# v1.net
KiCad netlist of a schematic drawn in EAGLE
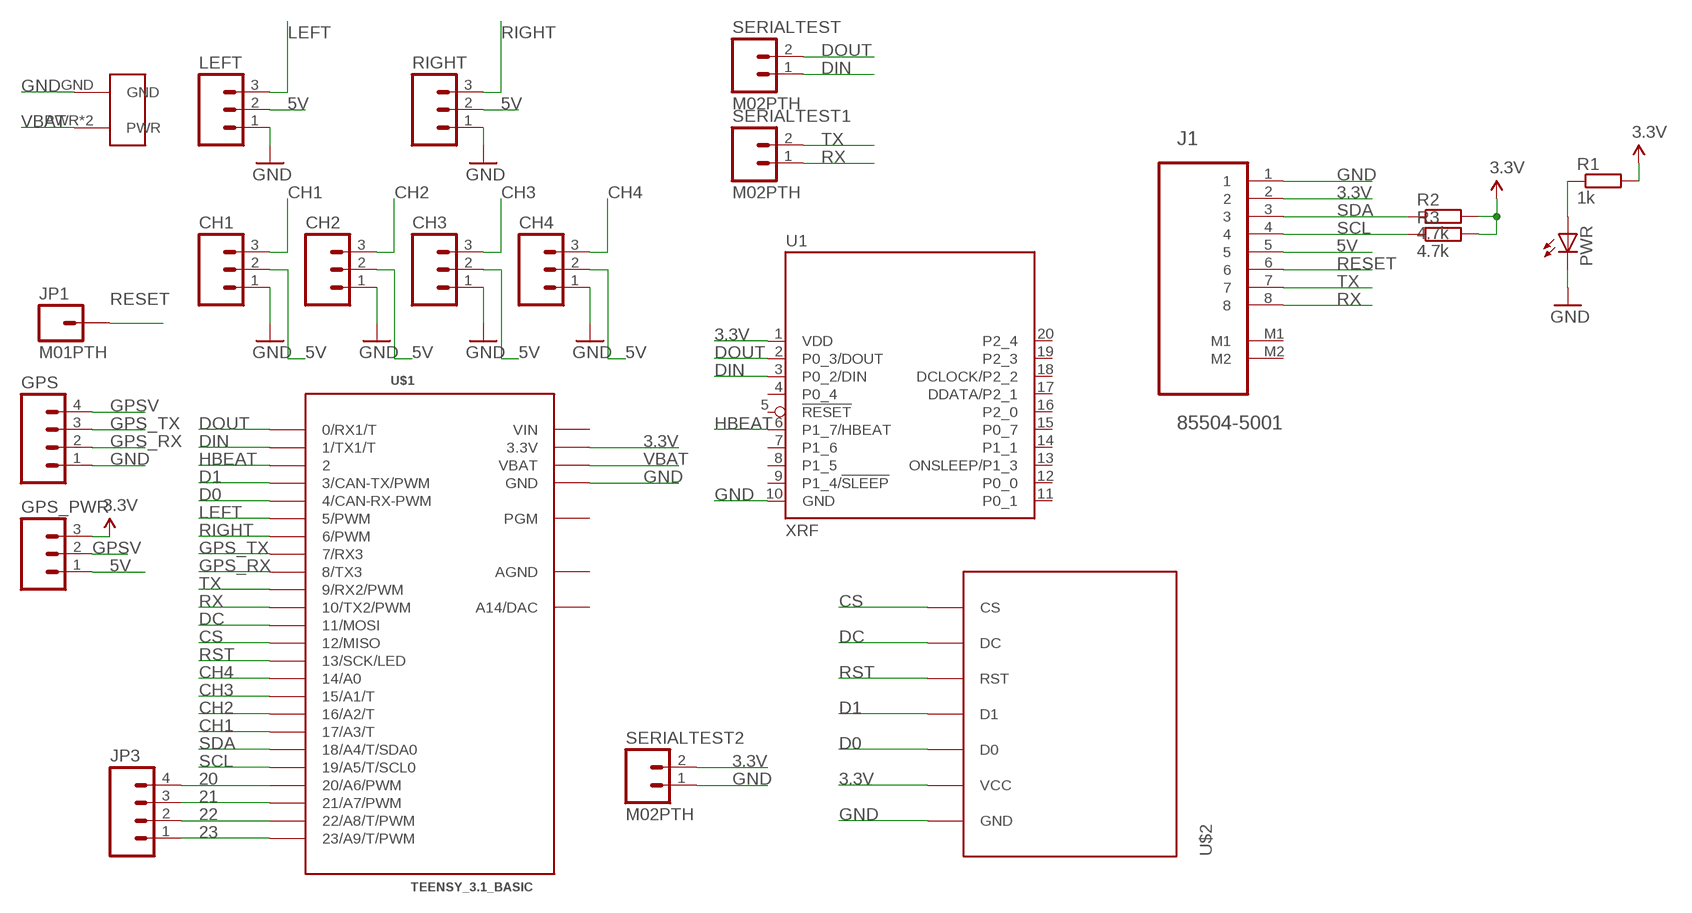
[diagram p0: schematic, sheet 1]

(export (version "E")
  (design (tool "Eeschema 10.0.6"))
  (components
    (comp (ref "CH1")
      (value "M03PTH")
      (footprint "eagle-import:1X03")
      (libsource (lib "eagle-import") (part "M03PTH"))
    )
    (comp (ref "CH2")
      (value "M03PTH")
      (footprint "eagle-import:1X03")
      (libsource (lib "eagle-import") (part "M03PTH"))
    )
    (comp (ref "CH3")
      (value "M03PTH")
      (footprint "eagle-import:1X03")
      (libsource (lib "eagle-import") (part "M03PTH"))
    )
    (comp (ref "CH4")
      (value "M03PTH")
      (footprint "eagle-import:1X03")
      (libsource (lib "eagle-import") (part "M03PTH"))
    )
    (comp (ref "GPS")
      (value "M04PTH")
      (footprint "eagle-import:1X04")
      (libsource (lib "eagle-import") (part "M04PTH"))
    )
    (comp (ref "GPS_PWR")
      (value "M03PTH")
      (footprint "eagle-import:1X03")
      (libsource (lib "eagle-import") (part "M03PTH"))
    )
    (comp (ref "J1")
      (value "85504-5001")
      (footprint "eagle-import:MOLEX_85504-5001")
      (libsource (lib "eagle-import") (part "85504-5001"))
    )
    (comp (ref "JP1")
      (value "M01PTH")
      (footprint "eagle-import:1X01")
      (libsource (lib "eagle-import") (part "M01PTH"))
    )
    (comp (ref "JP3")
      (value "M04PTH")
      (footprint "eagle-import:1X04")
      (libsource (lib "eagle-import") (part "M04PTH"))
    )
    (comp (ref "LEFT")
      (value "M03PTH")
      (footprint "eagle-import:1X03")
      (libsource (lib "eagle-import") (part "M03PTH"))
    )
    (comp (ref "PWR")
      (value "LEDCHIPLED_0805")
      (footprint "eagle-import:CHIPLED_0805")
      (libsource (lib "eagle-import") (part "LEDCHIPLED_0805"))
    )
    (comp (ref "R1")
      (value "1k")
      (footprint "eagle-import:R0805")
      (libsource (lib "eagle-import") (part "R-EU_R0805"))
    )
    (comp (ref "R2")
      (value "4.7k")
      (footprint "eagle-import:R0805")
      (libsource (lib "eagle-import") (part "R-EU_R0805"))
    )
    (comp (ref "R3")
      (value "4.7k")
      (footprint "eagle-import:R0805")
      (libsource (lib "eagle-import") (part "R-EU_R0805"))
    )
    (comp (ref "RIGHT")
      (value "M03PTH")
      (footprint "eagle-import:1X03")
      (libsource (lib "eagle-import") (part "M03PTH"))
    )
    (comp (ref "SERIALTEST")
      (value "M02PTH")
      (footprint "eagle-import:1X02")
      (libsource (lib "eagle-import") (part "M02PTH"))
    )
    (comp (ref "SERIALTEST1")
      (value "M02PTH")
      (footprint "eagle-import:1X02")
      (libsource (lib "eagle-import") (part "M02PTH"))
    )
    (comp (ref "SERIALTEST2")
      (value "M02PTH")
      (footprint "eagle-import:1X02")
      (libsource (lib "eagle-import") (part "M02PTH"))
    )
    (comp (ref "U$1")
      (value "TEENSY_3.1_BASIC")
      (footprint "eagle-import:TEENSY_3.1_BASIC")
      (libsource (lib "eagle-import") (part "TEENSY_3.1_BASIC"))
    )
    (comp (ref "U$2")
      (value "OLED_SSD1306_SPI")
      (footprint "eagle-import:OLED_SSD1306_SPI")
      (libsource (lib "eagle-import") (part "OLED_SSD1306_SPI"))
    )
    (comp (ref "U$3")
      (value "COINCELL")
      (footprint "eagle-import:COINCELL")
      (libsource (lib "eagle-import") (part "COINCELL"))
    )
    (comp (ref "U1")
      (value "XRF")
      (footprint "eagle-import:XRF")
      (libsource (lib "eagle-import") (part "XRF"))
    )
  )
  (nets
    (net (code "1") (name "/5V") (class "Default")
      (node (ref "CH1") (pin "2") (pinfunction "2_2") (pintype "passive"))
      (node (ref "CH2") (pin "2") (pinfunction "2_2") (pintype "passive"))
      (node (ref "CH3") (pin "2") (pinfunction "2_2") (pintype "passive"))
      (node (ref "CH4") (pin "2") (pinfunction "2_2") (pintype "passive"))
      (node (ref "GPS_PWR") (pin "1") (pinfunction "1_1") (pintype "passive"))
      (node (ref "J1") (pin "5") (pinfunction "5_5") (pintype "bidirectional"))
      (node (ref "LEFT") (pin "2") (pinfunction "2_2") (pintype "passive"))
      (node (ref "RIGHT") (pin "2") (pinfunction "2_2") (pintype "passive"))
    )
    (net (code "2") (name "/20") (class "Default")
      (node (ref "JP3") (pin "4") (pinfunction "4_4") (pintype "passive"))
      (node (ref "U$1") (pin "20/A6") (pinfunction "20/A6/PWM_20/A6") (pintype "bidirectional"))
    )
    (net (code "3") (name "/21") (class "Default")
      (node (ref "JP3") (pin "3") (pinfunction "3_3") (pintype "passive"))
      (node (ref "U$1") (pin "21/A7") (pinfunction "21/A7/PWM_21/A7") (pintype "bidirectional"))
    )
    (net (code "4") (name "/22") (class "Default")
      (node (ref "JP3") (pin "2") (pinfunction "2_2") (pintype "passive"))
      (node (ref "U$1") (pin "22/A8") (pinfunction "22/A8/T/PWM_22/A8") (pintype "bidirectional"))
    )
    (net (code "5") (name "/23") (class "Default")
      (node (ref "JP3") (pin "1") (pinfunction "1_1") (pintype "passive"))
      (node (ref "U$1") (pin "23/A9") (pinfunction "23/A9/T/PWM_23/A9") (pintype "bidirectional"))
    )
    (net (code "6") (name "/AGND") (class "Default")
      (node (ref "U$1") (pin "AGND") (pinfunction "AGND_AGND") (pintype "power_in"))
    )
    (net (code "7") (name "/CH1") (class "Default")
      (node (ref "CH1") (pin "3") (pinfunction "3_3") (pintype "passive"))
      (node (ref "U$1") (pin "17/A3") (pinfunction "17/A3/T_17/A3") (pintype "bidirectional"))
    )
    (net (code "8") (name "/CH2") (class "Default")
      (node (ref "CH2") (pin "3") (pinfunction "3_3") (pintype "passive"))
      (node (ref "U$1") (pin "16/A2") (pinfunction "16/A2/T_16/A2") (pintype "bidirectional"))
    )
    (net (code "9") (name "/CH3") (class "Default")
      (node (ref "CH3") (pin "3") (pinfunction "3_3") (pintype "passive"))
      (node (ref "U$1") (pin "15/A1") (pinfunction "15/A1/T_15/A1") (pintype "bidirectional"))
    )
    (net (code "10") (name "/CH4") (class "Default")
      (node (ref "CH4") (pin "3") (pinfunction "3_3") (pintype "passive"))
      (node (ref "U$1") (pin "14/A0") (pinfunction "14/A0_14/A0") (pintype "bidirectional"))
    )
    (net (code "11") (name "/CS") (class "Default")
      (node (ref "U$1") (pin "12") (pinfunction "12/MISO_12") (pintype "bidirectional"))
      (node (ref "U$2") (pin "CS") (pinfunction "CS_CS") (pintype "bidirectional"))
    )
    (net (code "12") (name "/D0") (class "Default")
      (node (ref "U$1") (pin "4") (pinfunction "4/CAN-RX-PWM_4") (pintype "bidirectional"))
      (node (ref "U$2") (pin "D0") (pinfunction "D0_D0") (pintype "bidirectional"))
    )
    (net (code "13") (name "/D1") (class "Default")
      (node (ref "U$1") (pin "3") (pinfunction "3/CAN-TX/PWM_3") (pintype "bidirectional"))
      (node (ref "U$2") (pin "D1") (pinfunction "D1_D1") (pintype "bidirectional"))
    )
    (net (code "14") (name "/DC") (class "Default")
      (node (ref "U$1") (pin "11") (pinfunction "11/MOSI_11") (pintype "bidirectional"))
      (node (ref "U$2") (pin "DC") (pinfunction "DC_DC") (pintype "bidirectional"))
    )
    (net (code "15") (name "/DIN") (class "Default")
      (node (ref "SERIALTEST") (pin "1") (pinfunction "1_1") (pintype "passive"))
      (node (ref "U$1") (pin "1") (pinfunction "1/TX1/T_1") (pintype "bidirectional"))
      (node (ref "U1") (pin "3") (pinfunction "P0_2/DIN_3") (pintype "input"))
    )
    (net (code "16") (name "/DOUT") (class "Default")
      (node (ref "SERIALTEST") (pin "2") (pinfunction "2_2") (pintype "passive"))
      (node (ref "U$1") (pin "0") (pinfunction "0/RX1/T_0") (pintype "bidirectional"))
      (node (ref "U1") (pin "2") (pinfunction "P0_3/DOUT_2") (pintype "output"))
    )
    (net (code "17") (name "/GPSV") (class "Default")
      (node (ref "GPS") (pin "4") (pinfunction "4_4") (pintype "passive"))
      (node (ref "GPS_PWR") (pin "2") (pinfunction "2_2") (pintype "passive"))
    )
    (net (code "18") (name "/GPS_RX") (class "Default")
      (node (ref "GPS") (pin "2") (pinfunction "2_2") (pintype "passive"))
      (node (ref "U$1") (pin "8") (pinfunction "8/TX3_8") (pintype "bidirectional"))
    )
    (net (code "19") (name "/GPS_TX") (class "Default")
      (node (ref "GPS") (pin "3") (pinfunction "3_3") (pintype "passive"))
      (node (ref "U$1") (pin "7") (pinfunction "7/RX3_7") (pintype "bidirectional"))
    )
    (net (code "20") (name "/HBEAT") (class "Default")
      (node (ref "U$1") (pin "2") (pinfunction "2_2") (pintype "bidirectional"))
      (node (ref "U1") (pin "6") (pinfunction "P1_7/HBEAT_6") (pintype "bidirectional"))
    )
    (net (code "21") (name "/LEFT") (class "Default")
      (node (ref "LEFT") (pin "3") (pinfunction "3_3") (pintype "passive"))
      (node (ref "U$1") (pin "5") (pinfunction "5/PWM_5") (pintype "bidirectional"))
    )
    (net (code "22") (name "/RESET") (class "Default")
      (node (ref "J1") (pin "6") (pinfunction "6_6") (pintype "bidirectional"))
      (node (ref "JP1") (pin "1") (pinfunction "1_1") (pintype "passive"))
    )
    (net (code "23") (name "/RIGHT") (class "Default")
      (node (ref "RIGHT") (pin "3") (pinfunction "3_3") (pintype "passive"))
      (node (ref "U$1") (pin "6") (pinfunction "6/PWM_6") (pintype "bidirectional"))
    )
    (net (code "24") (name "/RST") (class "Default")
      (node (ref "U$1") (pin "13") (pinfunction "13/SCK/LED_13") (pintype "bidirectional"))
      (node (ref "U$2") (pin "RST") (pinfunction "RST_RST") (pintype "bidirectional"))
    )
    (net (code "25") (name "/RX") (class "Default")
      (node (ref "J1") (pin "8") (pinfunction "8_8") (pintype "bidirectional"))
      (node (ref "SERIALTEST1") (pin "1") (pinfunction "1_1") (pintype "passive"))
      (node (ref "U$1") (pin "10") (pinfunction "10/TX2/PWM_10") (pintype "bidirectional"))
    )
    (net (code "26") (name "/SCL") (class "Default")
      (node (ref "J1") (pin "4") (pinfunction "4_4") (pintype "bidirectional"))
      (node (ref "R3") (pin "1") (pinfunction "1_1") (pintype "passive"))
      (node (ref "U$1") (pin "19/A5") (pinfunction "19/A5/T/SCL0_19/A5") (pintype "bidirectional"))
    )
    (net (code "27") (name "/SDA") (class "Default")
      (node (ref "J1") (pin "3") (pinfunction "3_3") (pintype "bidirectional"))
      (node (ref "R2") (pin "1") (pinfunction "1_1") (pintype "passive"))
      (node (ref "U$1") (pin "18/A4") (pinfunction "18/A4/T/SDA0_18/A4") (pintype "bidirectional"))
    )
    (net (code "28") (name "/TX") (class "Default")
      (node (ref "J1") (pin "7") (pinfunction "7_7") (pintype "bidirectional"))
      (node (ref "SERIALTEST1") (pin "2") (pinfunction "2_2") (pintype "passive"))
      (node (ref "U$1") (pin "9") (pinfunction "9/RX2/PWM_9") (pintype "bidirectional"))
    )
    (net (code "29") (name "/VBAT") (class "Default")
      (node (ref "U$1") (pin "VBAT") (pinfunction "VBAT_VBAT") (pintype "power_in"))
      (node (ref "U$3") (pin "PWR") (pinfunction "PWR_PWR") (pintype "bidirectional"))
      (node (ref "U$3") (pin "PWR2") (pinfunction "PWR_PWR2") (pintype "bidirectional"))
    )
    (net (code "30") (name "/VIN") (class "Default")
      (node (ref "U$1") (pin "VIN") (pinfunction "VIN_VIN") (pintype "power_in"))
    )
    (net (code "31") (name "3.3V") (class "Default")
      (node (ref "GPS_PWR") (pin "3") (pinfunction "3_3") (pintype "passive"))
      (node (ref "J1") (pin "2") (pinfunction "2_2") (pintype "bidirectional"))
      (node (ref "R1") (pin "2") (pinfunction "2_2") (pintype "passive"))
      (node (ref "R2") (pin "2") (pinfunction "2_2") (pintype "passive"))
      (node (ref "R3") (pin "2") (pinfunction "2_2") (pintype "passive"))
      (node (ref "SERIALTEST2") (pin "2") (pinfunction "2_2") (pintype "passive"))
      (node (ref "U$1") (pin "3.3V") (pinfunction "3.3V_3.3V") (pintype "power_in"))
      (node (ref "U$1") (pin "3.3V1") (pinfunction "3.3V_3.3V1") (pintype "power_in"))
      (node (ref "U$2") (pin "VCC") (pinfunction "VCC_VCC") (pintype "bidirectional"))
      (node (ref "U1") (pin "1") (pinfunction "VDD_1") (pintype "power_in"))
    )
    (net (code "32") (name "GND") (class "Default")
      (node (ref "CH1") (pin "1") (pinfunction "1_1") (pintype "passive"))
      (node (ref "CH2") (pin "1") (pinfunction "1_1") (pintype "passive"))
      (node (ref "CH3") (pin "1") (pinfunction "1_1") (pintype "passive"))
      (node (ref "CH4") (pin "1") (pinfunction "1_1") (pintype "passive"))
      (node (ref "GPS") (pin "1") (pinfunction "1_1") (pintype "passive"))
      (node (ref "J1") (pin "1") (pinfunction "1_1") (pintype "bidirectional"))
      (node (ref "LEFT") (pin "1") (pinfunction "1_1") (pintype "passive"))
      (node (ref "PWR") (pin "C") (pinfunction "C_C") (pintype "passive"))
      (node (ref "RIGHT") (pin "1") (pinfunction "1_1") (pintype "passive"))
      (node (ref "SERIALTEST2") (pin "1") (pinfunction "1_1") (pintype "passive"))
      (node (ref "U$1") (pin "GND") (pinfunction "GND_GND") (pintype "power_in"))
      (node (ref "U$1") (pin "GND1") (pinfunction "GND_GND1") (pintype "power_in"))
      (node (ref "U$2") (pin "GND") (pinfunction "GND_GND") (pintype "bidirectional"))
      (node (ref "U$3") (pin "GND") (pinfunction "GND_GND") (pintype "bidirectional"))
      (node (ref "U1") (pin "10") (pinfunction "GND_10") (pintype "power_in"))
    )
    (net (code "33") (name "Net-(PWR-PadA)") (class "Default")
      (node (ref "PWR") (pin "A") (pinfunction "A_A") (pintype "passive"))
      (node (ref "R1") (pin "1") (pinfunction "1_1") (pintype "passive"))
    )
    (net (code "34") (name "unconnected-(J1-PadM1)") (class "Default")
      (node (ref "J1") (pin "M1") (pinfunction "M1_M1") (pintype "bidirectional"))
    )
    (net (code "35") (name "unconnected-(J1-PadM2)") (class "Default")
      (node (ref "J1") (pin "M2") (pinfunction "M2_M2") (pintype "bidirectional"))
    )
    (net (code "36") (name "unconnected-(U$1-A14{slash}DAC-PadA14)") (class "Default")
      (node (ref "U$1") (pin "A14") (pinfunction "A14/DAC_A14") (pintype "bidirectional"))
    )
    (net (code "37") (name "unconnected-(U$1-PadPGM)") (class "Default")
      (node (ref "U$1") (pin "PGM") (pinfunction "PGM_PGM") (pintype "bidirectional"))
    )
    (net (code "38") (name "unconnected-(U1-DCLOCK{slash}P2_2-Pad18)") (class "Default")
      (node (ref "U1") (pin "18") (pinfunction "DCLOCK/P2_2_18") (pintype "bidirectional"))
    )
    (net (code "39") (name "unconnected-(U1-DDATA{slash}P2_1-Pad17)") (class "Default")
      (node (ref "U1") (pin "17") (pinfunction "DDATA/P2_1_17") (pintype "bidirectional"))
    )
    (net (code "40") (name "unconnected-(U1-ONSLEEP{slash}P1_3-Pad13)") (class "Default")
      (node (ref "U1") (pin "13") (pinfunction "ONSLEEP/P1_3_13") (pintype "bidirectional"))
    )
    (net (code "41") (name "unconnected-(U1-P0_0-Pad12)") (class "Default")
      (node (ref "U1") (pin "12") (pinfunction "P0_0_12") (pintype "bidirectional"))
    )
    (net (code "42") (name "unconnected-(U1-P0_1-Pad11)") (class "Default")
      (node (ref "U1") (pin "11") (pinfunction "P0_1_11") (pintype "bidirectional"))
    )
    (net (code "43") (name "unconnected-(U1-P0_4-Pad4)") (class "Default")
      (node (ref "U1") (pin "4") (pinfunction "P0_4_4") (pintype "bidirectional"))
    )
    (net (code "44") (name "unconnected-(U1-P0_7-Pad15)") (class "Default")
      (node (ref "U1") (pin "15") (pinfunction "P0_7_15") (pintype "bidirectional"))
    )
    (net (code "45") (name "unconnected-(U1-P1_1-Pad14)") (class "Default")
      (node (ref "U1") (pin "14") (pinfunction "P1_1_14") (pintype "bidirectional"))
    )
    (net (code "46") (name "unconnected-(U1-P1_4{slash}~{SLEEP}-Pad9)") (class "Default")
      (node (ref "U1") (pin "9") (pinfunction "P1_4/~{SLEEP}_9") (pintype "bidirectional"))
    )
    (net (code "47") (name "unconnected-(U1-P1_5-Pad8)") (class "Default")
      (node (ref "U1") (pin "8") (pinfunction "P1_5_8") (pintype "bidirectional"))
    )
    (net (code "48") (name "unconnected-(U1-P1_6-Pad7)") (class "Default")
      (node (ref "U1") (pin "7") (pinfunction "P1_6_7") (pintype "bidirectional"))
    )
    (net (code "49") (name "unconnected-(U1-P2_0-Pad16)") (class "Default")
      (node (ref "U1") (pin "16") (pinfunction "P2_0_16") (pintype "input"))
    )
    (net (code "50") (name "unconnected-(U1-P2_3-Pad19)") (class "Default")
      (node (ref "U1") (pin "19") (pinfunction "P2_3_19") (pintype "bidirectional"))
    )
    (net (code "51") (name "unconnected-(U1-P2_4-Pad20)") (class "Default")
      (node (ref "U1") (pin "20") (pinfunction "P2_4_20") (pintype "bidirectional"))
    )
    (net (code "52") (name "unconnected-(U1-~{RESET}-Pad5)") (class "Default")
      (node (ref "U1") (pin "5") (pinfunction "~{RESET}_5") (pintype "input"))
    )
  )
)
